# Adafruit_ST7565.net
KiCad netlist of a schematic drawn in EAGLE
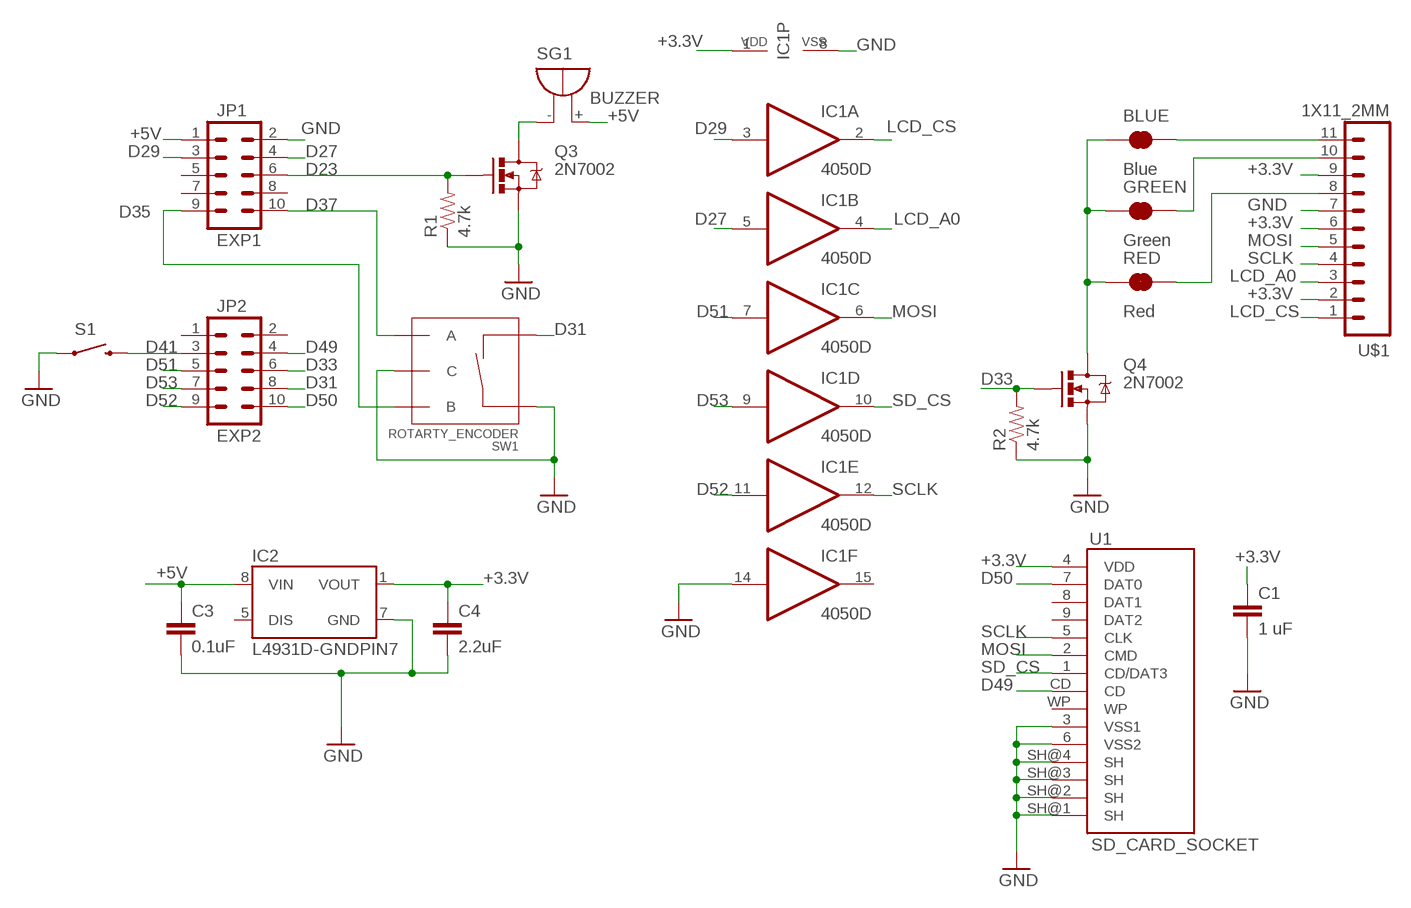
[diagram p0: schematic, sheet 1]

(export (version "E")
  (design (tool "Eeschema 10.0.6"))
  (components
    (comp (ref "BLUE")
      (value "Blue")
      (footprint "eagle-import:PAD-JUMPER-2-NC_BY_TRACE_YES_SILK")
      (libsource (lib "eagle-import") (part "JUMPER-PAD-2-NC_BY_TRACE"))
    )
    (comp (ref "C1")
      (value "1 uF")
      (footprint "eagle-import:1206")
      (libsource (lib "eagle-import") (part "CAP1206"))
    )
    (comp (ref "C3")
      (value "0.1uF")
      (footprint "eagle-import:1206")
      (libsource (lib "eagle-import") (part "CAP1206"))
    )
    (comp (ref "C4")
      (value "2.2uF")
      (footprint "eagle-import:1206")
      (libsource (lib "eagle-import") (part "CAP1206"))
    )
    (comp (ref "GREEN")
      (value "Green")
      (footprint "eagle-import:PAD-JUMPER-2-NC_BY_TRACE_YES_SILK")
      (libsource (lib "eagle-import") (part "JUMPER-PAD-2-NC_BY_TRACE"))
    )
    (comp (ref "IC1")
      (value "4050D")
      (footprint "eagle-import:SO16")
      (libsource (lib "eagle-import") (part "4050D"))
    )
    (comp (ref "IC2")
      (value "L4931D-GNDPIN7")
      (footprint "eagle-import:SO08")
      (libsource (lib "eagle-import") (part "L4931D-GNDPIN7"))
    )
    (comp (ref "JP1")
      (value "EXP1")
      (footprint "eagle-import:2X5-SHROUDED")
      (libsource (lib "eagle-import") (part "M05X2SHD"))
    )
    (comp (ref "JP2")
      (value "EXP2")
      (footprint "eagle-import:2X5-SHROUDED")
      (libsource (lib "eagle-import") (part "M05X2SHD"))
    )
    (comp (ref "Q3")
      (value "2N7002")
      (footprint "eagle-import:SOT23-3")
      (libsource (lib "eagle-import") (part "MOSFET-NCHANNELBSS123LT1G"))
    )
    (comp (ref "Q4")
      (value "2N7002")
      (footprint "eagle-import:SOT23-3")
      (libsource (lib "eagle-import") (part "MOSFET-NCHANNELBSS123LT1G"))
    )
    (comp (ref "R1")
      (value "4.7k")
      (footprint "eagle-import:1206")
      (libsource (lib "eagle-import") (part "RESISTOR1206"))
    )
    (comp (ref "R2")
      (value "4.7k")
      (footprint "eagle-import:1206")
      (libsource (lib "eagle-import") (part "RESISTOR1206"))
    )
    (comp (ref "RED")
      (value "Red")
      (footprint "eagle-import:PAD-JUMPER-2-NC_BY_TRACE_YES_SILK")
      (libsource (lib "eagle-import") (part "JUMPER-PAD-2-NC_BY_TRACE"))
    )
    (comp (ref "S1")
      (value "SWITCH-MOMENTARY-2PTH")
      (footprint "eagle-import:TACTILE-PTH")
      (libsource (lib "eagle-import") (part "SWITCH-MOMENTARY-2PTH"))
    )
    (comp (ref "SG1")
      (value "BUZZER")
      (footprint "eagle-import:F_QMBIII")
      (libsource (lib "eagle-import") (part "BUZZER"))
    )
    (comp (ref "SW1")
      (value "ROTARTY_ENCODER")
      (footprint "eagle-import:ROTARY_ENC_PLAIN")
      (libsource (lib "eagle-import") (part "ROTARTY_ENCODER"))
    )
    (comp (ref "U$1")
      (value "1X11_2MM")
      (footprint "eagle-import:1X11_2MM")
      (libsource (lib "eagle-import") (part "1X11_2MM"))
    )
    (comp (ref "U1")
      (value "SD_CARD_SOCKET")
      (footprint "eagle-import:SD_1_1")
      (libsource (lib "eagle-import") (part "SD_CARD_SOCKET"))
    )
  )
  (nets
    (net (code "1") (name "/+3.3V") (class "Default")
      (node (ref "C1") (pin "1") (pinfunction "1_1") (pintype "passive"))
      (node (ref "C4") (pin "1") (pinfunction "1_1") (pintype "passive"))
      (node (ref "IC1") (pin "1") (pinfunction "VDD_1") (pintype "power_in"))
      (node (ref "IC2") (pin "1") (pinfunction "VOUT_1") (pintype "power_in"))
      (node (ref "U$1") (pin "2") (pinfunction "P$2_2") (pintype "passive"))
      (node (ref "U$1") (pin "6") (pinfunction "P$6_6") (pintype "passive"))
      (node (ref "U$1") (pin "9") (pinfunction "P$9_9") (pintype "passive"))
      (node (ref "U1") (pin "4") (pinfunction "VDD_4") (pintype "power_in"))
    )
    (net (code "2") (name "/+5V") (class "Default")
      (node (ref "C3") (pin "1") (pinfunction "1_1") (pintype "passive"))
      (node (ref "IC2") (pin "8") (pinfunction "VIN_8") (pintype "power_in"))
      (node (ref "JP1") (pin "1") (pinfunction "1_1") (pintype "passive"))
      (node (ref "SG1") (pin "+") (pinfunction "-_+") (pintype "passive"))
    )
    (net (code "3") (name "/D23") (class "Default")
      (node (ref "JP1") (pin "6") (pinfunction "6_6") (pintype "passive"))
      (node (ref "Q3") (pin "1") (pinfunction "G_1") (pintype "passive"))
      (node (ref "R1") (pin "2") (pinfunction "2_2") (pintype "passive"))
    )
    (net (code "4") (name "/D27") (class "Default")
      (node (ref "IC1") (pin "5") (pinfunction "I_5") (pintype "input"))
      (node (ref "JP1") (pin "4") (pinfunction "4_4") (pintype "passive"))
    )
    (net (code "5") (name "/D29") (class "Default")
      (node (ref "IC1") (pin "3") (pinfunction "I_3") (pintype "input"))
      (node (ref "JP1") (pin "3") (pinfunction "3_3") (pintype "passive"))
    )
    (net (code "6") (name "/D31") (class "Default")
      (node (ref "JP2") (pin "8") (pinfunction "8_8") (pintype "passive"))
      (node (ref "SW1") (pin "SW-") (pinfunction "SW-_SW-") (pintype "bidirectional"))
    )
    (net (code "7") (name "/D33") (class "Default")
      (node (ref "JP2") (pin "6") (pinfunction "6_6") (pintype "passive"))
      (node (ref "Q4") (pin "1") (pinfunction "G_1") (pintype "passive"))
      (node (ref "R2") (pin "2") (pinfunction "2_2") (pintype "passive"))
    )
    (net (code "8") (name "/D35") (class "Default")
      (node (ref "JP1") (pin "9") (pinfunction "9_9") (pintype "passive"))
      (node (ref "SW1") (pin "B") (pinfunction "B_B") (pintype "bidirectional"))
    )
    (net (code "9") (name "/D37") (class "Default")
      (node (ref "JP1") (pin "10") (pinfunction "10_10") (pintype "passive"))
      (node (ref "SW1") (pin "A") (pinfunction "A_A") (pintype "bidirectional"))
    )
    (net (code "10") (name "/D41") (class "Default")
      (node (ref "JP2") (pin "3") (pinfunction "3_3") (pintype "passive"))
      (node (ref "S1") (pin "3") (pinfunction "2_3") (pintype "passive"))
    )
    (net (code "11") (name "/D49") (class "Default")
      (node (ref "JP2") (pin "4") (pinfunction "4_4") (pintype "passive"))
      (node (ref "U1") (pin "CD") (pinfunction "CD_CD") (pintype "bidirectional"))
    )
    (net (code "12") (name "/D50") (class "Default")
      (node (ref "JP2") (pin "10") (pinfunction "10_10") (pintype "passive"))
      (node (ref "U1") (pin "7") (pinfunction "DAT0_7") (pintype "bidirectional"))
    )
    (net (code "13") (name "/D51") (class "Default")
      (node (ref "IC1") (pin "7") (pinfunction "I_7") (pintype "input"))
      (node (ref "JP2") (pin "5") (pinfunction "5_5") (pintype "passive"))
    )
    (net (code "14") (name "/D52") (class "Default")
      (node (ref "IC1") (pin "11") (pinfunction "I_11") (pintype "input"))
      (node (ref "JP2") (pin "9") (pinfunction "9_9") (pintype "passive"))
    )
    (net (code "15") (name "/D53") (class "Default")
      (node (ref "IC1") (pin "9") (pinfunction "I_9") (pintype "input"))
      (node (ref "JP2") (pin "7") (pinfunction "7_7") (pintype "passive"))
    )
    (net (code "16") (name "/LCD_A0") (class "Default")
      (node (ref "IC1") (pin "4") (pinfunction "O_4") (pintype "output"))
      (node (ref "U$1") (pin "3") (pinfunction "P$3_3") (pintype "passive"))
    )
    (net (code "17") (name "/LCD_CS") (class "Default")
      (node (ref "IC1") (pin "2") (pinfunction "O_2") (pintype "output"))
      (node (ref "U$1") (pin "1") (pinfunction "P$1_1") (pintype "passive"))
    )
    (net (code "18") (name "/MOSI") (class "Default")
      (node (ref "IC1") (pin "6") (pinfunction "O_6") (pintype "output"))
      (node (ref "U$1") (pin "5") (pinfunction "P$5_5") (pintype "passive"))
      (node (ref "U1") (pin "2") (pinfunction "CMD_2") (pintype "bidirectional"))
    )
    (net (code "19") (name "/SCLK") (class "Default")
      (node (ref "IC1") (pin "12") (pinfunction "O_12") (pintype "output"))
      (node (ref "U$1") (pin "4") (pinfunction "P$4_4") (pintype "passive"))
      (node (ref "U1") (pin "5") (pinfunction "CLK_5") (pintype "bidirectional"))
    )
    (net (code "20") (name "/SD_CS") (class "Default")
      (node (ref "IC1") (pin "10") (pinfunction "O_10") (pintype "output"))
      (node (ref "U1") (pin "1") (pinfunction "CD/DAT3_1") (pintype "bidirectional"))
    )
    (net (code "21") (name "GND") (class "Default")
      (node (ref "C1") (pin "2") (pinfunction "2_2") (pintype "passive"))
      (node (ref "C3") (pin "2") (pinfunction "2_2") (pintype "passive"))
      (node (ref "C4") (pin "2") (pinfunction "2_2") (pintype "passive"))
      (node (ref "IC1") (pin "14") (pinfunction "I_14") (pintype "input"))
      (node (ref "IC1") (pin "8") (pinfunction "VSS_8") (pintype "power_in"))
      (node (ref "IC2") (pin "7") (pinfunction "GND_7") (pintype "power_in"))
      (node (ref "JP1") (pin "2") (pinfunction "2_2") (pintype "passive"))
      (node (ref "Q3") (pin "2") (pinfunction "S_2") (pintype "passive"))
      (node (ref "Q4") (pin "2") (pinfunction "S_2") (pintype "passive"))
      (node (ref "R1") (pin "1") (pinfunction "1_1") (pintype "passive"))
      (node (ref "R2") (pin "1") (pinfunction "1_1") (pintype "passive"))
      (node (ref "S1") (pin "1") (pinfunction "1_1") (pintype "passive"))
      (node (ref "SW1") (pin "C") (pinfunction "C_C") (pintype "bidirectional"))
      (node (ref "SW1") (pin "SW+") (pinfunction "SW+_SW+") (pintype "bidirectional"))
      (node (ref "U$1") (pin "7") (pinfunction "P$7_7") (pintype "passive"))
      (node (ref "U1") (pin "3") (pinfunction "VSS1_3") (pintype "power_in"))
      (node (ref "U1") (pin "6") (pinfunction "VSS2_6") (pintype "power_in"))
      (node (ref "U1") (pin "SH@1") (pinfunction "SH_SH@1") (pintype "bidirectional"))
      (node (ref "U1") (pin "SH@2") (pinfunction "SH_SH@2") (pintype "bidirectional"))
      (node (ref "U1") (pin "SH@3") (pinfunction "SH_SH@3") (pintype "bidirectional"))
      (node (ref "U1") (pin "SH@4") (pinfunction "SH_SH@4") (pintype "bidirectional"))
    )
    (net (code "22") (name "Net-(Q3-D)") (class "Default")
      (node (ref "Q3") (pin "3") (pinfunction "D_3") (pintype "passive"))
      (node (ref "SG1") (pin "-") (pinfunction "+_-") (pintype "passive"))
    )
    (net (code "23") (name "Net-(Q4-D)") (class "Default")
      (node (ref "BLUE") (pin "1") (pinfunction "1_1") (pintype "passive"))
      (node (ref "GREEN") (pin "1") (pinfunction "1_1") (pintype "passive"))
      (node (ref "Q4") (pin "3") (pinfunction "D_3") (pintype "passive"))
      (node (ref "RED") (pin "1") (pinfunction "1_1") (pintype "passive"))
    )
    (net (code "24") (name "Net-(U$1-P$8)") (class "Default")
      (node (ref "RED") (pin "2") (pinfunction "2_2") (pintype "passive"))
      (node (ref "U$1") (pin "8") (pinfunction "P$8_8") (pintype "passive"))
    )
    (net (code "25") (name "Net-(U$1-P$10)") (class "Default")
      (node (ref "GREEN") (pin "2") (pinfunction "2_2") (pintype "passive"))
      (node (ref "U$1") (pin "10") (pinfunction "P$10_10") (pintype "passive"))
    )
    (net (code "26") (name "Net-(U$1-P$11)") (class "Default")
      (node (ref "BLUE") (pin "2") (pinfunction "2_2") (pintype "passive"))
      (node (ref "U$1") (pin "11") (pinfunction "P$11_11") (pintype "passive"))
    )
    (net (code "27") (name "unconnected-(IC1F-O-Pad15)") (class "Default")
      (node (ref "IC1") (pin "15") (pinfunction "O_15") (pintype "output"))
    )
    (net (code "28") (name "unconnected-(IC2-DIS-Pad5)") (class "Default")
      (node (ref "IC2") (pin "5") (pinfunction "DIS_5") (pintype "passive"))
    )
    (net (code "29") (name "unconnected-(JP1-Pad5)") (class "Default")
      (node (ref "JP1") (pin "5") (pinfunction "5_5") (pintype "passive"))
    )
    (net (code "30") (name "unconnected-(JP1-Pad7)") (class "Default")
      (node (ref "JP1") (pin "7") (pinfunction "7_7") (pintype "passive"))
    )
    (net (code "31") (name "unconnected-(JP1-Pad8)") (class "Default")
      (node (ref "JP1") (pin "8") (pinfunction "8_8") (pintype "passive"))
    )
    (net (code "32") (name "unconnected-(JP2-Pad1)") (class "Default")
      (node (ref "JP2") (pin "1") (pinfunction "1_1") (pintype "passive"))
    )
    (net (code "33") (name "unconnected-(JP2-Pad2)") (class "Default")
      (node (ref "JP2") (pin "2") (pinfunction "2_2") (pintype "passive"))
    )
    (net (code "34") (name "unconnected-(U1-DAT1-Pad8)") (class "Default")
      (node (ref "U1") (pin "8") (pinfunction "DAT1_8") (pintype "bidirectional"))
    )
    (net (code "35") (name "unconnected-(U1-DAT2-Pad9)") (class "Default")
      (node (ref "U1") (pin "9") (pinfunction "DAT2_9") (pintype "bidirectional"))
    )
    (net (code "36") (name "unconnected-(U1-PadWP)") (class "Default")
      (node (ref "U1") (pin "WP") (pinfunction "WP_WP") (pintype "bidirectional"))
    )
  )
)
